# DRV5032AJLPGM.net
KiCad netlist of a schematic drawn in Altium Designer
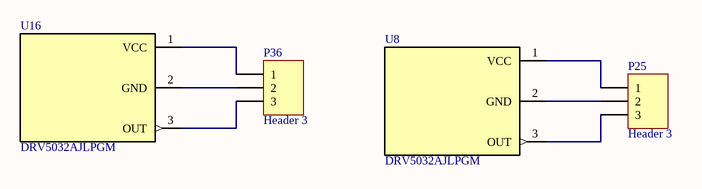
[diagram p0: DRV5032AJLPGM.SchDoc]

(export (version "E")
  (design (tool "Eeschema 10.0.6"))
  (components
    (comp (ref "P25")
      (value "Header 3")
      (footprint "HDR1X3")
      (description "Header, 3-Pin")
      (fields (field (name "PUBLISHER") "Altium Limited"))
      (libsource (lib "Miscellaneous Connectors") (part "Header 3"))
    )
    (comp (ref "P36")
      (value "Header 3")
      (footprint "HDR1X3")
      (description "Header, 3-Pin")
      (fields (field (name "PUBLISHER") "Altium Limited"))
      (libsource (lib "Miscellaneous Connectors") (part "Header 3"))
    )
    (comp (ref "U8")
      (value "DRV5032AJLPGM")
      (footprint "SENSOR_DRV5055A2QLPGM")
      (description "Low power (5 Hz, <1ÂµA), low voltage (up to 5.5V) switch")
      (fields (field (name "MF") "Texas Instruments"))
      (libsource (lib "DRV5032AJLPGM") (part "DRV5032AJLPGM"))
    )
    (comp (ref "U16")
      (value "DRV5032AJLPGM")
      (footprint "SENSOR_DRV5055A2QLPGM")
      (description "Low power (5 Hz, <1ÂµA), low voltage (up to 5.5V) switch")
      (fields (field (name "MF") "Texas Instruments"))
      (libsource (lib "DRV5032AJLPGM") (part "DRV5032AJLPGM"))
    )
  )
  (nets
    (net (code "1") (name "Net-(U8-GND)") (class "Default")
      (node (ref "P25") (pin "2") (pinfunction "2_2") (pintype "passive"))
      (node (ref "U8") (pin "2") (pinfunction "GND_2") (pintype "power_in"))
    )
    (net (code "2") (name "Net-(U8-OUT)") (class "Default")
      (node (ref "P25") (pin "3") (pinfunction "3_3") (pintype "passive"))
      (node (ref "U8") (pin "3") (pinfunction "OUT_3") (pintype "output"))
    )
    (net (code "3") (name "Net-(U8-VCC)") (class "Default")
      (node (ref "P25") (pin "1") (pinfunction "1_1") (pintype "passive"))
      (node (ref "U8") (pin "1") (pinfunction "VCC_1") (pintype "power_in"))
    )
    (net (code "4") (name "Net-(U16-GND)") (class "Default")
      (node (ref "P36") (pin "2") (pinfunction "2_2") (pintype "passive"))
      (node (ref "U16") (pin "2") (pinfunction "GND_2") (pintype "power_in"))
    )
    (net (code "5") (name "Net-(U16-OUT)") (class "Default")
      (node (ref "P36") (pin "3") (pinfunction "3_3") (pintype "passive"))
      (node (ref "U16") (pin "3") (pinfunction "OUT_3") (pintype "output"))
    )
    (net (code "6") (name "Net-(U16-VCC)") (class "Default")
      (node (ref "P36") (pin "1") (pinfunction "1_1") (pintype "passive"))
      (node (ref "U16") (pin "1") (pinfunction "VCC_1") (pintype "power_in"))
    )
  )
)
